# W300C.net
KiCad netlist of a schematic drawn in EAGLE
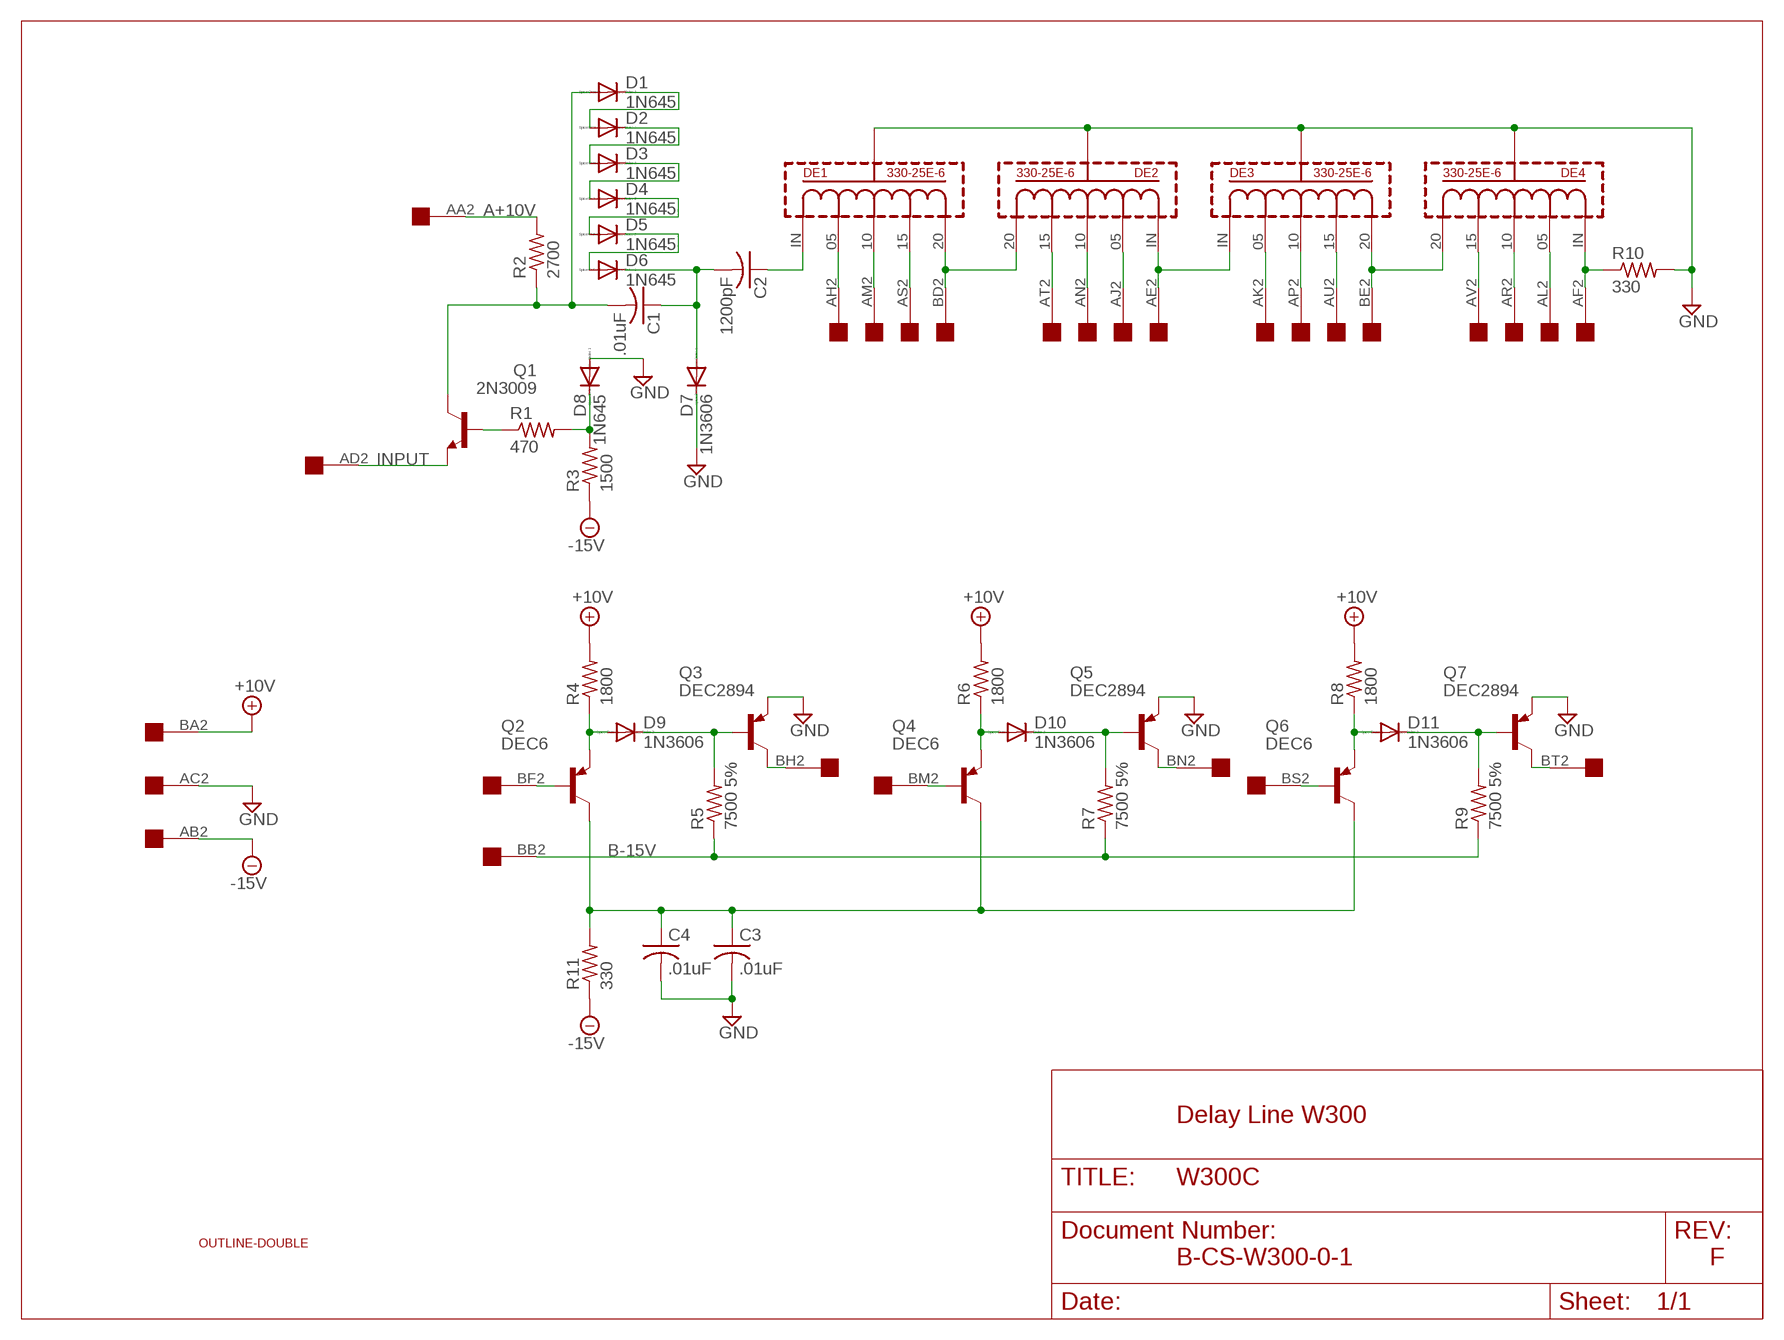
[diagram p0: schematic, sheet 1]

(export (version "E")
  (design (tool "Eeschema 10.0.6"))
  (components
    (comp (ref "C1")
      (value ".01uF")
      (footprint "eagle-import:C050-025X075")
      (libsource (lib "eagle-import") (part "C-US050-025X075"))
    )
    (comp (ref "C2")
      (value "1200pF")
      (footprint "eagle-import:C102-043X133")
      (libsource (lib "eagle-import") (part "C-US102-043X133"))
    )
    (comp (ref "C3")
      (value ".01uF")
      (footprint "eagle-import:C050-025X075")
      (libsource (lib "eagle-import") (part "C-US050-025X075"))
    )
    (comp (ref "C4")
      (value ".01uF")
      (footprint "eagle-import:C050-025X075")
      (libsource (lib "eagle-import") (part "C-US050-025X075"))
    )
    (comp (ref "D1")
      (value "1N645")
      (footprint "eagle-import:DO35-10")
      (libsource (lib "eagle-import") (part "1N4148DO35-10"))
    )
    (comp (ref "D2")
      (value "1N645")
      (footprint "eagle-import:DO35-10")
      (libsource (lib "eagle-import") (part "1N4148DO35-10"))
    )
    (comp (ref "D3")
      (value "1N645")
      (footprint "eagle-import:DO35-10")
      (libsource (lib "eagle-import") (part "1N4148DO35-10"))
    )
    (comp (ref "D4")
      (value "1N645")
      (footprint "eagle-import:DO35-10")
      (libsource (lib "eagle-import") (part "1N4148DO35-10"))
    )
    (comp (ref "D5")
      (value "1N645")
      (footprint "eagle-import:DO35-10")
      (libsource (lib "eagle-import") (part "1N4148DO35-10"))
    )
    (comp (ref "D6")
      (value "1N645")
      (footprint "eagle-import:DO35-10")
      (libsource (lib "eagle-import") (part "1N4148DO35-10"))
    )
    (comp (ref "D7")
      (value "1N3606")
      (footprint "eagle-import:DO35-10")
      (libsource (lib "eagle-import") (part "1N4148DO35-10"))
    )
    (comp (ref "D8")
      (value "1N645")
      (footprint "eagle-import:DO35-10")
      (libsource (lib "eagle-import") (part "1N4148DO35-10"))
    )
    (comp (ref "D9")
      (value "1N3606")
      (footprint "eagle-import:DO35-10")
      (libsource (lib "eagle-import") (part "1N4148DO35-10"))
    )
    (comp (ref "D10")
      (value "1N3606")
      (footprint "eagle-import:DO35-10")
      (libsource (lib "eagle-import") (part "1N4148DO35-10"))
    )
    (comp (ref "D11")
      (value "1N3606")
      (footprint "eagle-import:DO35-10")
      (libsource (lib "eagle-import") (part "1N4148DO35-10"))
    )
    (comp (ref "DE1")
      (value "330-25E-6")
      (footprint "eagle-import:330-25E")
      (libsource (lib "eagle-import") (part "330-25E"))
    )
    (comp (ref "DE2")
      (value "330-25E-6")
      (footprint "eagle-import:330-25E")
      (libsource (lib "eagle-import") (part "330-25E"))
    )
    (comp (ref "DE3")
      (value "330-25E-6")
      (footprint "eagle-import:330-25E")
      (libsource (lib "eagle-import") (part "330-25E"))
    )
    (comp (ref "DE4")
      (value "330-25E-6")
      (footprint "eagle-import:330-25E")
      (libsource (lib "eagle-import") (part "330-25E"))
    )
    (comp (ref "Q1")
      (value "2N3009")
      (footprint "eagle-import:TO5")
      (libsource (lib "eagle-import") (part "2N2219"))
    )
    (comp (ref "Q2")
      (value "DEC6")
      (footprint "eagle-import:TO5")
      (libsource (lib "eagle-import") (part "2N2905"))
    )
    (comp (ref "Q3")
      (value "DEC2894")
      (footprint "eagle-import:TO5")
      (libsource (lib "eagle-import") (part "2N2905"))
    )
    (comp (ref "Q4")
      (value "DEC6")
      (footprint "eagle-import:TO5")
      (libsource (lib "eagle-import") (part "2N2905"))
    )
    (comp (ref "Q5")
      (value "DEC2894")
      (footprint "eagle-import:TO5")
      (libsource (lib "eagle-import") (part "2N2905"))
    )
    (comp (ref "Q6")
      (value "DEC6")
      (footprint "eagle-import:TO5")
      (libsource (lib "eagle-import") (part "2N2905"))
    )
    (comp (ref "Q7")
      (value "DEC2894")
      (footprint "eagle-import:TO5")
      (libsource (lib "eagle-import") (part "2N2905"))
    )
    (comp (ref "R1")
      (value "470")
      (footprint "eagle-import:0207_10")
      (libsource (lib "eagle-import") (part "R-US_0207/10"))
    )
    (comp (ref "R2")
      (value "2700")
      (footprint "eagle-import:0207_10")
      (libsource (lib "eagle-import") (part "R-US_0207/10"))
    )
    (comp (ref "R3")
      (value "1500")
      (footprint "eagle-import:0207_10")
      (libsource (lib "eagle-import") (part "R-US_0207/10"))
    )
    (comp (ref "R4")
      (value "1800")
      (footprint "eagle-import:0207_10")
      (libsource (lib "eagle-import") (part "R-US_0207/10"))
    )
    (comp (ref "R5")
      (value "7500 5%")
      (footprint "eagle-import:0207_10")
      (libsource (lib "eagle-import") (part "R-US_0207/10"))
    )
    (comp (ref "R6")
      (value "1800")
      (footprint "eagle-import:0207_10")
      (libsource (lib "eagle-import") (part "R-US_0207/10"))
    )
    (comp (ref "R7")
      (value "7500 5%")
      (footprint "eagle-import:0207_10")
      (libsource (lib "eagle-import") (part "R-US_0207/10"))
    )
    (comp (ref "R8")
      (value "1800")
      (footprint "eagle-import:0207_10")
      (libsource (lib "eagle-import") (part "R-US_0207/10"))
    )
    (comp (ref "R9")
      (value "7500 5%")
      (footprint "eagle-import:0207_10")
      (libsource (lib "eagle-import") (part "R-US_0207/10"))
    )
    (comp (ref "R10")
      (value "330")
      (footprint "eagle-import:0207_10")
      (libsource (lib "eagle-import") (part "R-US_0207/10"))
    )
    (comp (ref "R11")
      (value "330")
      (footprint "eagle-import:0207_10")
      (libsource (lib "eagle-import") (part "R-US_0207/10"))
    )
    (comp (ref "U$1")
      (value "OUTLINE-DOUBLE")
      (footprint "eagle-import:DOUBLE")
      (libsource (lib "eagle-import") (part "OUTLINE-DOUBLE"))
    )
    (comp (ref "U$3")
      (value "DOUBLE")
      (footprint "eagle-import:EDGE-CON4")
      (libsource (lib "eagle-import") (part "DOUBLE"))
    )
  )
  (nets
    (net (code "1") (name "+10V") (class "Default")
      (node (ref "R4") (pin "2") (pinfunction "2_2") (pintype "passive"))
      (node (ref "R6") (pin "2") (pinfunction "2_2") (pintype "passive"))
      (node (ref "R8") (pin "2") (pinfunction "2_2") (pintype "passive"))
      (node (ref "U$3") (pin "BA2") (pinfunction "1_BA2") (pintype "bidirectional"))
    )
    (net (code "2") (name "-15V") (class "Default")
      (node (ref "R11") (pin "1") (pinfunction "1_1") (pintype "passive"))
      (node (ref "R3") (pin "1") (pinfunction "1_1") (pintype "passive"))
      (node (ref "U$3") (pin "AB2") (pinfunction "1_AB2") (pintype "bidirectional"))
    )
    (net (code "3") (name "/A+10V") (class "Default")
      (node (ref "R2") (pin "2") (pinfunction "2_2") (pintype "passive"))
      (node (ref "U$3") (pin "AA2") (pinfunction "1_AA2") (pintype "bidirectional"))
    )
    (net (code "4") (name "/B-15V") (class "Default")
      (node (ref "R5") (pin "1") (pinfunction "1_1") (pintype "passive"))
      (node (ref "R7") (pin "1") (pinfunction "1_1") (pintype "passive"))
      (node (ref "R9") (pin "1") (pinfunction "1_1") (pintype "passive"))
      (node (ref "U$3") (pin "BB2") (pinfunction "1_BB2") (pintype "bidirectional"))
    )
    (net (code "5") (name "/INPUT") (class "Default")
      (node (ref "Q1") (pin "1") (pinfunction "E_1") (pintype "passive"))
      (node (ref "U$3") (pin "AD2") (pinfunction "1_AD2") (pintype "bidirectional"))
    )
    (net (code "6") (name "GND") (class "Default")
      (node (ref "C3") (pin "2") (pinfunction "2_2") (pintype "passive"))
      (node (ref "C4") (pin "2") (pinfunction "2_2") (pintype "passive"))
      (node (ref "D7") (pin "C") (pinfunction "C_C") (pintype "passive"))
      (node (ref "D8") (pin "A") (pinfunction "A_A") (pintype "passive"))
      (node (ref "DE1") (pin "GND") (pinfunction "GND_GND") (pintype "passive"))
      (node (ref "DE2") (pin "GND") (pinfunction "GND_GND") (pintype "passive"))
      (node (ref "DE3") (pin "GND") (pinfunction "GND_GND") (pintype "passive"))
      (node (ref "DE4") (pin "GND") (pinfunction "GND_GND") (pintype "passive"))
      (node (ref "Q3") (pin "1") (pinfunction "E_1") (pintype "passive"))
      (node (ref "Q5") (pin "1") (pinfunction "E_1") (pintype "passive"))
      (node (ref "Q7") (pin "1") (pinfunction "E_1") (pintype "passive"))
      (node (ref "R10") (pin "2") (pinfunction "2_2") (pintype "passive"))
      (node (ref "U$3") (pin "AC2") (pinfunction "1_AC2") (pintype "bidirectional"))
    )
    (net (code "7") (name "Net-(C1-Pad1)") (class "Default")
      (node (ref "C1") (pin "1") (pinfunction "1_1") (pintype "passive"))
      (node (ref "C2") (pin "2") (pinfunction "2_2") (pintype "passive"))
      (node (ref "D6") (pin "C") (pinfunction "C_C") (pintype "passive"))
      (node (ref "D7") (pin "A") (pinfunction "A_A") (pintype "passive"))
    )
    (net (code "8") (name "Net-(D1-PadC)") (class "Default")
      (node (ref "D1") (pin "C") (pinfunction "C_C") (pintype "passive"))
      (node (ref "D2") (pin "A") (pinfunction "A_A") (pintype "passive"))
    )
    (net (code "9") (name "Net-(D2-PadC)") (class "Default")
      (node (ref "D2") (pin "C") (pinfunction "C_C") (pintype "passive"))
      (node (ref "D3") (pin "A") (pinfunction "A_A") (pintype "passive"))
    )
    (net (code "10") (name "Net-(D3-PadC)") (class "Default")
      (node (ref "D3") (pin "C") (pinfunction "C_C") (pintype "passive"))
      (node (ref "D4") (pin "A") (pinfunction "A_A") (pintype "passive"))
    )
    (net (code "11") (name "Net-(D4-PadC)") (class "Default")
      (node (ref "D4") (pin "C") (pinfunction "C_C") (pintype "passive"))
      (node (ref "D5") (pin "A") (pinfunction "A_A") (pintype "passive"))
    )
    (net (code "12") (name "Net-(D5-PadC)") (class "Default")
      (node (ref "D5") (pin "C") (pinfunction "C_C") (pintype "passive"))
      (node (ref "D6") (pin "A") (pinfunction "A_A") (pintype "passive"))
    )
    (net (code "13") (name "Net-(D8-PadC)") (class "Default")
      (node (ref "D8") (pin "C") (pinfunction "C_C") (pintype "passive"))
      (node (ref "R1") (pin "2") (pinfunction "2_2") (pintype "passive"))
      (node (ref "R3") (pin "2") (pinfunction "2_2") (pintype "passive"))
    )
    (net (code "14") (name "Net-(DE1-0)") (class "Default")
      (node (ref "C2") (pin "1") (pinfunction "1_1") (pintype "passive"))
      (node (ref "DE1") (pin "IN") (pinfunction "0_IN") (pintype "passive"))
    )
    (net (code "15") (name "Net-(DE1-5)") (class "Default")
      (node (ref "DE1") (pin "05") (pinfunction "5_05") (pintype "passive"))
      (node (ref "U$3") (pin "AH2") (pinfunction "1_AH2") (pintype "bidirectional"))
    )
    (net (code "16") (name "Net-(DE2-0)") (class "Default")
      (node (ref "DE2") (pin "IN") (pinfunction "0_IN") (pintype "passive"))
      (node (ref "DE3") (pin "IN") (pinfunction "0_IN") (pintype "passive"))
      (node (ref "U$3") (pin "AE2") (pinfunction "1_AE2") (pintype "bidirectional"))
    )
    (net (code "17") (name "Net-(DE2-5)") (class "Default")
      (node (ref "DE2") (pin "05") (pinfunction "5_05") (pintype "passive"))
      (node (ref "U$3") (pin "AJ2") (pinfunction "1_AJ2") (pintype "bidirectional"))
    )
    (net (code "18") (name "Net-(DE3-5)") (class "Default")
      (node (ref "DE3") (pin "05") (pinfunction "5_05") (pintype "passive"))
      (node (ref "U$3") (pin "AK2") (pinfunction "1_AK2") (pintype "bidirectional"))
    )
    (net (code "19") (name "Net-(DE4-0)") (class "Default")
      (node (ref "DE4") (pin "IN") (pinfunction "0_IN") (pintype "passive"))
      (node (ref "R10") (pin "1") (pinfunction "1_1") (pintype "passive"))
      (node (ref "U$3") (pin "AF2") (pinfunction "1_AF2") (pintype "bidirectional"))
    )
    (net (code "20") (name "Net-(DE4-5)") (class "Default")
      (node (ref "DE4") (pin "05") (pinfunction "5_05") (pintype "passive"))
      (node (ref "U$3") (pin "AL2") (pinfunction "1_AL2") (pintype "bidirectional"))
    )
    (net (code "21") (name "Net-(Q1-B)") (class "Default")
      (node (ref "Q1") (pin "2") (pinfunction "B_2") (pintype "passive"))
      (node (ref "R1") (pin "1") (pinfunction "1_1") (pintype "passive"))
    )
    (net (code "22") (name "Net-(Q1-C)") (class "Default")
      (node (ref "C1") (pin "2") (pinfunction "2_2") (pintype "passive"))
      (node (ref "D1") (pin "A") (pinfunction "A_A") (pintype "passive"))
      (node (ref "Q1") (pin "3") (pinfunction "C_3") (pintype "passive"))
      (node (ref "R2") (pin "1") (pinfunction "1_1") (pintype "passive"))
    )
    (net (code "23") (name "Net-(Q2-B)") (class "Default")
      (node (ref "Q2") (pin "2") (pinfunction "B_2") (pintype "passive"))
      (node (ref "U$3") (pin "BF2") (pinfunction "1_BF2") (pintype "bidirectional"))
    )
    (net (code "24") (name "Net-(Q2-C)") (class "Default")
      (node (ref "C3") (pin "1") (pinfunction "1_1") (pintype "passive"))
      (node (ref "C4") (pin "1") (pinfunction "1_1") (pintype "passive"))
      (node (ref "Q2") (pin "3") (pinfunction "C_3") (pintype "passive"))
      (node (ref "Q4") (pin "3") (pinfunction "C_3") (pintype "passive"))
      (node (ref "Q6") (pin "3") (pinfunction "C_3") (pintype "passive"))
      (node (ref "R11") (pin "2") (pinfunction "2_2") (pintype "passive"))
    )
    (net (code "25") (name "Net-(Q2-E)") (class "Default")
      (node (ref "D9") (pin "A") (pinfunction "A_A") (pintype "passive"))
      (node (ref "Q2") (pin "1") (pinfunction "E_1") (pintype "passive"))
      (node (ref "R4") (pin "1") (pinfunction "1_1") (pintype "passive"))
    )
    (net (code "26") (name "Net-(Q3-B)") (class "Default")
      (node (ref "D9") (pin "C") (pinfunction "C_C") (pintype "passive"))
      (node (ref "Q3") (pin "2") (pinfunction "B_2") (pintype "passive"))
      (node (ref "R5") (pin "2") (pinfunction "2_2") (pintype "passive"))
    )
    (net (code "27") (name "Net-(Q3-C)") (class "Default")
      (node (ref "Q3") (pin "3") (pinfunction "C_3") (pintype "passive"))
      (node (ref "U$3") (pin "BH2") (pinfunction "1_BH2") (pintype "bidirectional"))
    )
    (net (code "28") (name "Net-(Q4-B)") (class "Default")
      (node (ref "Q4") (pin "2") (pinfunction "B_2") (pintype "passive"))
      (node (ref "U$3") (pin "BM2") (pinfunction "1_BM2") (pintype "bidirectional"))
    )
    (net (code "29") (name "Net-(Q4-E)") (class "Default")
      (node (ref "D10") (pin "A") (pinfunction "A_A") (pintype "passive"))
      (node (ref "Q4") (pin "1") (pinfunction "E_1") (pintype "passive"))
      (node (ref "R6") (pin "1") (pinfunction "1_1") (pintype "passive"))
    )
    (net (code "30") (name "Net-(Q5-B)") (class "Default")
      (node (ref "D10") (pin "C") (pinfunction "C_C") (pintype "passive"))
      (node (ref "Q5") (pin "2") (pinfunction "B_2") (pintype "passive"))
      (node (ref "R7") (pin "2") (pinfunction "2_2") (pintype "passive"))
    )
    (net (code "31") (name "Net-(Q5-C)") (class "Default")
      (node (ref "Q5") (pin "3") (pinfunction "C_3") (pintype "passive"))
      (node (ref "U$3") (pin "BN2") (pinfunction "1_BN2") (pintype "bidirectional"))
    )
    (net (code "32") (name "Net-(Q6-B)") (class "Default")
      (node (ref "Q6") (pin "2") (pinfunction "B_2") (pintype "passive"))
      (node (ref "U$3") (pin "BS2") (pinfunction "1_BS2") (pintype "bidirectional"))
    )
    (net (code "33") (name "Net-(Q6-E)") (class "Default")
      (node (ref "D11") (pin "A") (pinfunction "A_A") (pintype "passive"))
      (node (ref "Q6") (pin "1") (pinfunction "E_1") (pintype "passive"))
      (node (ref "R8") (pin "1") (pinfunction "1_1") (pintype "passive"))
    )
    (net (code "34") (name "Net-(Q7-B)") (class "Default")
      (node (ref "D11") (pin "C") (pinfunction "C_C") (pintype "passive"))
      (node (ref "Q7") (pin "2") (pinfunction "B_2") (pintype "passive"))
      (node (ref "R9") (pin "2") (pinfunction "2_2") (pintype "passive"))
    )
    (net (code "35") (name "Net-(Q7-C)") (class "Default")
      (node (ref "Q7") (pin "3") (pinfunction "C_3") (pintype "passive"))
      (node (ref "U$3") (pin "BT2") (pinfunction "1_BT2") (pintype "bidirectional"))
    )
    (net (code "36") (name "Net-(U$3AB-1)") (class "Default")
      (node (ref "DE4") (pin "10") (pinfunction "10_10") (pintype "passive"))
      (node (ref "U$3") (pin "AR2") (pinfunction "1_AR2") (pintype "bidirectional"))
    )
    (net (code "37") (name "Net-(U$3AD-1)") (class "Default")
      (node (ref "DE1") (pin "15") (pinfunction "15_15") (pintype "passive"))
      (node (ref "U$3") (pin "AS2") (pinfunction "1_AS2") (pintype "bidirectional"))
    )
    (net (code "38") (name "Net-(U$3AF-1)") (class "Default")
      (node (ref "DE2") (pin "15") (pinfunction "15_15") (pintype "passive"))
      (node (ref "U$3") (pin "AT2") (pinfunction "1_AT2") (pintype "bidirectional"))
    )
    (net (code "39") (name "Net-(U$3AH-1)") (class "Default")
      (node (ref "DE3") (pin "15") (pinfunction "15_15") (pintype "passive"))
      (node (ref "U$3") (pin "AU2") (pinfunction "1_AU2") (pintype "bidirectional"))
    )
    (net (code "40") (name "Net-(U$3AJ-1)") (class "Default")
      (node (ref "DE4") (pin "15") (pinfunction "15_15") (pintype "passive"))
      (node (ref "U$3") (pin "AV2") (pinfunction "1_AV2") (pintype "bidirectional"))
    )
    (net (code "41") (name "Net-(U$3AR-1)") (class "Default")
      (node (ref "DE1") (pin "20") (pinfunction "20_20") (pintype "passive"))
      (node (ref "DE2") (pin "20") (pinfunction "20_20") (pintype "passive"))
      (node (ref "U$3") (pin "BD2") (pinfunction "1_BD2") (pintype "bidirectional"))
    )
    (net (code "42") (name "Net-(U$3AT-1)") (class "Default")
      (node (ref "DE3") (pin "20") (pinfunction "20_20") (pintype "passive"))
      (node (ref "DE4") (pin "20") (pinfunction "20_20") (pintype "passive"))
      (node (ref "U$3") (pin "BE2") (pinfunction "1_BE2") (pintype "bidirectional"))
    )
    (net (code "43") (name "Net-(U$3V-1)") (class "Default")
      (node (ref "DE1") (pin "10") (pinfunction "10_10") (pintype "passive"))
      (node (ref "U$3") (pin "AM2") (pinfunction "1_AM2") (pintype "bidirectional"))
    )
    (net (code "44") (name "Net-(U$3X-1)") (class "Default")
      (node (ref "DE2") (pin "10") (pinfunction "10_10") (pintype "passive"))
      (node (ref "U$3") (pin "AN2") (pinfunction "1_AN2") (pintype "bidirectional"))
    )
    (net (code "45") (name "Net-(U$3Z-1)") (class "Default")
      (node (ref "DE3") (pin "10") (pinfunction "10_10") (pintype "passive"))
      (node (ref "U$3") (pin "AP2") (pinfunction "1_AP2") (pintype "bidirectional"))
    )
  )
)
